# A500_2MB.net
KiCad netlist of a schematic drawn in EAGLE
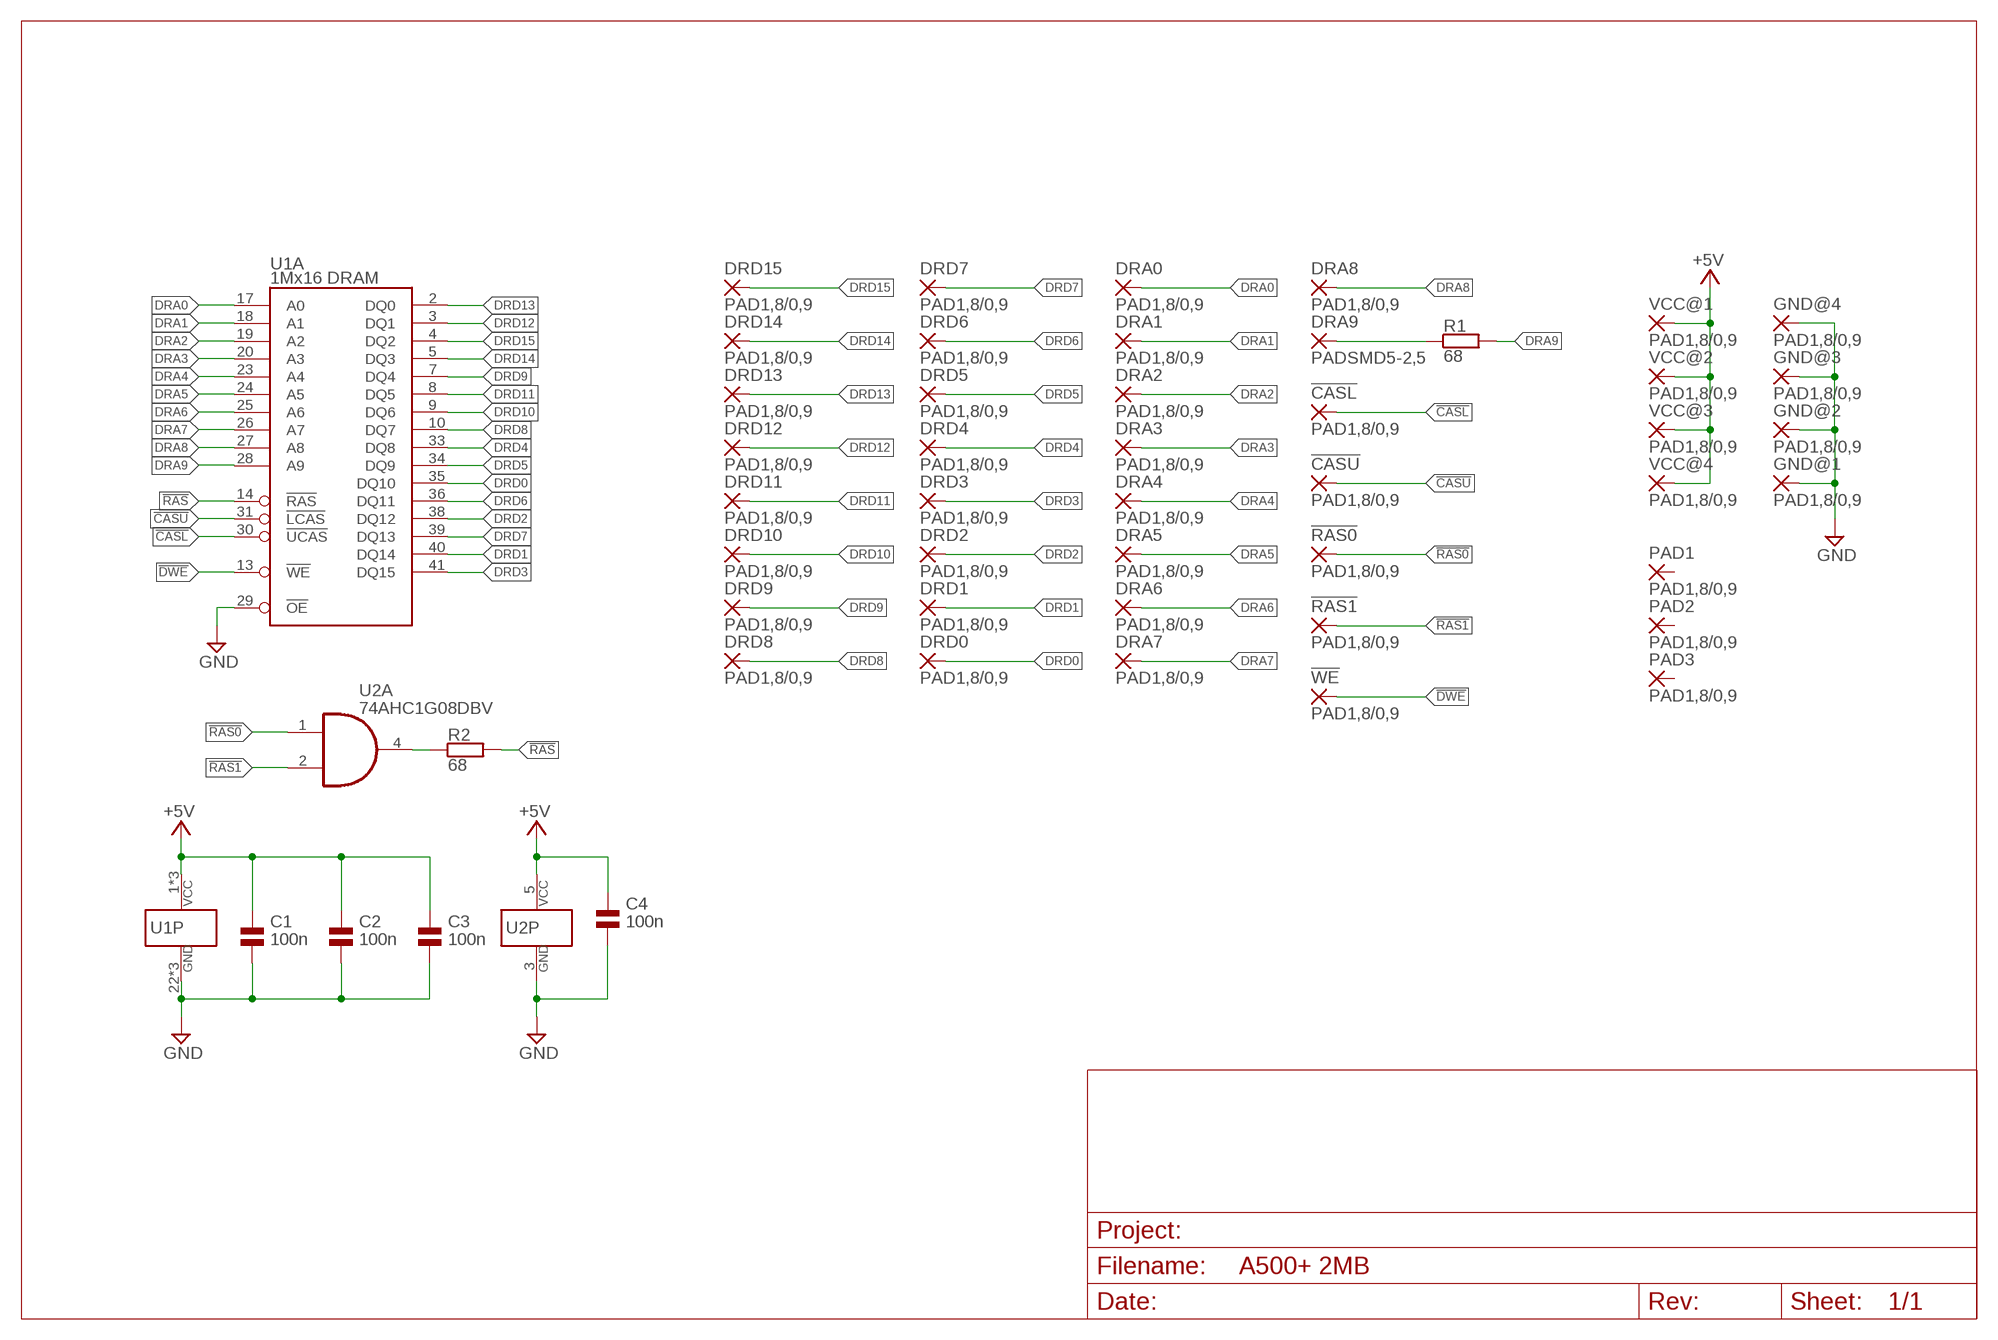
[diagram p0: schematic, sheet 1]

(export (version "E")
  (design (tool "Eeschema 10.0.6"))
  (components
    (comp (ref "!CASL")
      (value "PAD1,8/0,9")
      (footprint "eagle-import:1,8_0,9")
      (libsource (lib "eagle-import") (part "PAD1,8/0,9"))
    )
    (comp (ref "!CASU")
      (value "PAD1,8/0,9")
      (footprint "eagle-import:1,8_0,9")
      (libsource (lib "eagle-import") (part "PAD1,8/0,9"))
    )
    (comp (ref "!RAS0")
      (value "PAD1,8/0,9")
      (footprint "eagle-import:1,8_0,9")
      (libsource (lib "eagle-import") (part "PAD1,8/0,9"))
    )
    (comp (ref "!RAS1")
      (value "PAD1,8/0,9")
      (footprint "eagle-import:1,8_0,9")
      (libsource (lib "eagle-import") (part "PAD1,8/0,9"))
    )
    (comp (ref "!WE")
      (value "PAD1,8/0,9")
      (footprint "eagle-import:1,8_0,9")
      (libsource (lib "eagle-import") (part "PAD1,8/0,9"))
    )
    (comp (ref "C1")
      (value "100n")
      (footprint "eagle-import:0603")
      (libsource (lib "eagle-import") (part "CAP_NPOL0603-"))
    )
    (comp (ref "C2")
      (value "100n")
      (footprint "eagle-import:0603")
      (libsource (lib "eagle-import") (part "CAP_NPOL0603-"))
    )
    (comp (ref "C3")
      (value "100n")
      (footprint "eagle-import:0603")
      (libsource (lib "eagle-import") (part "CAP_NPOL0603-"))
    )
    (comp (ref "C4")
      (value "100n")
      (footprint "eagle-import:0603")
      (libsource (lib "eagle-import") (part "CAP_NPOL0603-"))
    )
    (comp (ref "DRA0")
      (value "PAD1,8/0,9")
      (footprint "eagle-import:1,8_0,9")
      (libsource (lib "eagle-import") (part "PAD1,8/0,9"))
    )
    (comp (ref "DRA1")
      (value "PAD1,8/0,9")
      (footprint "eagle-import:1,8_0,9")
      (libsource (lib "eagle-import") (part "PAD1,8/0,9"))
    )
    (comp (ref "DRA2")
      (value "PAD1,8/0,9")
      (footprint "eagle-import:1,8_0,9")
      (libsource (lib "eagle-import") (part "PAD1,8/0,9"))
    )
    (comp (ref "DRA3")
      (value "PAD1,8/0,9")
      (footprint "eagle-import:1,8_0,9")
      (libsource (lib "eagle-import") (part "PAD1,8/0,9"))
    )
    (comp (ref "DRA4")
      (value "PAD1,8/0,9")
      (footprint "eagle-import:1,8_0,9")
      (libsource (lib "eagle-import") (part "PAD1,8/0,9"))
    )
    (comp (ref "DRA5")
      (value "PAD1,8/0,9")
      (footprint "eagle-import:1,8_0,9")
      (libsource (lib "eagle-import") (part "PAD1,8/0,9"))
    )
    (comp (ref "DRA6")
      (value "PAD1,8/0,9")
      (footprint "eagle-import:1,8_0,9")
      (libsource (lib "eagle-import") (part "PAD1,8/0,9"))
    )
    (comp (ref "DRA7")
      (value "PAD1,8/0,9")
      (footprint "eagle-import:1,8_0,9")
      (libsource (lib "eagle-import") (part "PAD1,8/0,9"))
    )
    (comp (ref "DRA8")
      (value "PAD1,8/0,9")
      (footprint "eagle-import:1,8_0,9")
      (libsource (lib "eagle-import") (part "PAD1,8/0,9"))
    )
    (comp (ref "DRA9")
      (value "PADSMD5-2,5")
      (footprint "eagle-import:5-2,5")
      (libsource (lib "eagle-import") (part "PADSMD5-2,5"))
    )
    (comp (ref "DRD0")
      (value "PAD1,8/0,9")
      (footprint "eagle-import:1,8_0,9")
      (libsource (lib "eagle-import") (part "PAD1,8/0,9"))
    )
    (comp (ref "DRD1")
      (value "PAD1,8/0,9")
      (footprint "eagle-import:1,8_0,9")
      (libsource (lib "eagle-import") (part "PAD1,8/0,9"))
    )
    (comp (ref "DRD2")
      (value "PAD1,8/0,9")
      (footprint "eagle-import:1,8_0,9")
      (libsource (lib "eagle-import") (part "PAD1,8/0,9"))
    )
    (comp (ref "DRD3")
      (value "PAD1,8/0,9")
      (footprint "eagle-import:1,8_0,9")
      (libsource (lib "eagle-import") (part "PAD1,8/0,9"))
    )
    (comp (ref "DRD4")
      (value "PAD1,8/0,9")
      (footprint "eagle-import:1,8_0,9")
      (libsource (lib "eagle-import") (part "PAD1,8/0,9"))
    )
    (comp (ref "DRD5")
      (value "PAD1,8/0,9")
      (footprint "eagle-import:1,8_0,9")
      (libsource (lib "eagle-import") (part "PAD1,8/0,9"))
    )
    (comp (ref "DRD6")
      (value "PAD1,8/0,9")
      (footprint "eagle-import:1,8_0,9")
      (libsource (lib "eagle-import") (part "PAD1,8/0,9"))
    )
    (comp (ref "DRD7")
      (value "PAD1,8/0,9")
      (footprint "eagle-import:1,8_0,9")
      (libsource (lib "eagle-import") (part "PAD1,8/0,9"))
    )
    (comp (ref "DRD8")
      (value "PAD1,8/0,9")
      (footprint "eagle-import:1,8_0,9")
      (libsource (lib "eagle-import") (part "PAD1,8/0,9"))
    )
    (comp (ref "DRD9")
      (value "PAD1,8/0,9")
      (footprint "eagle-import:1,8_0,9")
      (libsource (lib "eagle-import") (part "PAD1,8/0,9"))
    )
    (comp (ref "DRD10")
      (value "PAD1,8/0,9")
      (footprint "eagle-import:1,8_0,9")
      (libsource (lib "eagle-import") (part "PAD1,8/0,9"))
    )
    (comp (ref "DRD11")
      (value "PAD1,8/0,9")
      (footprint "eagle-import:1,8_0,9")
      (libsource (lib "eagle-import") (part "PAD1,8/0,9"))
    )
    (comp (ref "DRD12")
      (value "PAD1,8/0,9")
      (footprint "eagle-import:1,8_0,9")
      (libsource (lib "eagle-import") (part "PAD1,8/0,9"))
    )
    (comp (ref "DRD13")
      (value "PAD1,8/0,9")
      (footprint "eagle-import:1,8_0,9")
      (libsource (lib "eagle-import") (part "PAD1,8/0,9"))
    )
    (comp (ref "DRD14")
      (value "PAD1,8/0,9")
      (footprint "eagle-import:1,8_0,9")
      (libsource (lib "eagle-import") (part "PAD1,8/0,9"))
    )
    (comp (ref "DRD15")
      (value "PAD1,8/0,9")
      (footprint "eagle-import:1,8_0,9")
      (libsource (lib "eagle-import") (part "PAD1,8/0,9"))
    )
    (comp (ref "GND@1")
      (value "PAD1,8/0,9")
      (footprint "eagle-import:1,8_0,9")
      (libsource (lib "eagle-import") (part "PAD1,8/0,9"))
    )
    (comp (ref "GND@2")
      (value "PAD1,8/0,9")
      (footprint "eagle-import:1,8_0,9")
      (libsource (lib "eagle-import") (part "PAD1,8/0,9"))
    )
    (comp (ref "GND@3")
      (value "PAD1,8/0,9")
      (footprint "eagle-import:1,8_0,9")
      (libsource (lib "eagle-import") (part "PAD1,8/0,9"))
    )
    (comp (ref "GND@4")
      (value "PAD1,8/0,9")
      (footprint "eagle-import:1,8_0,9")
      (libsource (lib "eagle-import") (part "PAD1,8/0,9"))
    )
    (comp (ref "PAD1")
      (value "PAD1,8/0,9")
      (footprint "eagle-import:1,8_0,9")
      (libsource (lib "eagle-import") (part "PAD1,8/0,9"))
    )
    (comp (ref "PAD2")
      (value "PAD1,8/0,9")
      (footprint "eagle-import:1,8_0,9")
      (libsource (lib "eagle-import") (part "PAD1,8/0,9"))
    )
    (comp (ref "PAD3")
      (value "PAD1,8/0,9")
      (footprint "eagle-import:1,8_0,9")
      (libsource (lib "eagle-import") (part "PAD1,8/0,9"))
    )
    (comp (ref "R1")
      (value "68")
      (footprint "eagle-import:0603")
      (libsource (lib "eagle-import") (part "RESSMD_0603-"))
    )
    (comp (ref "R2")
      (value "68")
      (footprint "eagle-import:0603")
      (libsource (lib "eagle-import") (part "RESSMD_0603-"))
    )
    (comp (ref "U1")
      (value "1Mx16 DRAM")
      (footprint "eagle-import:SOJ42_4")
      (libsource (lib "eagle-import") (part "DRAM_1MX16SOJ-"))
    )
    (comp (ref "U2")
      (value "74AHC1G08DBV")
      (footprint "eagle-import:SOT23-5")
      (libsource (lib "eagle-import") (part "741G08DBVAHC"))
    )
    (comp (ref "VCC@1")
      (value "PAD1,8/0,9")
      (footprint "eagle-import:1,8_0,9")
      (libsource (lib "eagle-import") (part "PAD1,8/0,9"))
    )
    (comp (ref "VCC@2")
      (value "PAD1,8/0,9")
      (footprint "eagle-import:1,8_0,9")
      (libsource (lib "eagle-import") (part "PAD1,8/0,9"))
    )
    (comp (ref "VCC@3")
      (value "PAD1,8/0,9")
      (footprint "eagle-import:1,8_0,9")
      (libsource (lib "eagle-import") (part "PAD1,8/0,9"))
    )
    (comp (ref "VCC@4")
      (value "PAD1,8/0,9")
      (footprint "eagle-import:1,8_0,9")
      (libsource (lib "eagle-import") (part "PAD1,8/0,9"))
    )
  )
  (nets
    (net (code "1") (name "+5V") (class "Default")
      (node (ref "C1") (pin "1") (pinfunction "1_1") (pintype "passive"))
      (node (ref "C2") (pin "1") (pinfunction "1_1") (pintype "passive"))
      (node (ref "C3") (pin "1") (pinfunction "1_1") (pintype "passive"))
      (node (ref "C4") (pin "1") (pinfunction "1_1") (pintype "passive"))
      (node (ref "U1") (pin "1") (pinfunction "VCC_1") (pintype "power_in"))
      (node (ref "U1") (pin "21") (pinfunction "VCC_21") (pintype "power_in"))
      (node (ref "U1") (pin "6") (pinfunction "VCC_6") (pintype "power_in"))
      (node (ref "U2") (pin "5") (pinfunction "VCC_5") (pintype "power_in"))
      (node (ref "VCC@1") (pin "1") (pinfunction "P_1") (pintype "passive"))
      (node (ref "VCC@2") (pin "1") (pinfunction "P_1") (pintype "passive"))
      (node (ref "VCC@3") (pin "1") (pinfunction "P_1") (pintype "passive"))
      (node (ref "VCC@4") (pin "1") (pinfunction "P_1") (pintype "passive"))
    )
    (net (code "2") (name "/~{CASL}") (class "Default")
      (node (ref "!CASL") (pin "1") (pinfunction "P_1") (pintype "passive"))
      (node (ref "U1") (pin "30") (pinfunction "~{UCAS}_30") (pintype "input"))
    )
    (net (code "3") (name "/~{CASU}") (class "Default")
      (node (ref "!CASU") (pin "1") (pinfunction "P_1") (pintype "passive"))
      (node (ref "U1") (pin "31") (pinfunction "~{LCAS}_31") (pintype "input"))
    )
    (net (code "4") (name "/~{DWE}") (class "Default")
      (node (ref "!WE") (pin "1") (pinfunction "P_1") (pintype "passive"))
      (node (ref "U1") (pin "13") (pinfunction "~{WE}_13") (pintype "input"))
    )
    (net (code "5") (name "/~{RAS0}") (class "Default")
      (node (ref "!RAS0") (pin "1") (pinfunction "P_1") (pintype "passive"))
      (node (ref "U2") (pin "1") (pinfunction "I0_1") (pintype "input"))
    )
    (net (code "6") (name "/~{RAS1}") (class "Default")
      (node (ref "!RAS1") (pin "1") (pinfunction "P_1") (pintype "passive"))
      (node (ref "U2") (pin "2") (pinfunction "I1_2") (pintype "input"))
    )
    (net (code "7") (name "/~{RAS}") (class "Default")
      (node (ref "R2") (pin "2") (pinfunction "2_2") (pintype "passive"))
      (node (ref "U1") (pin "14") (pinfunction "~{RAS}_14") (pintype "input"))
    )
    (net (code "8") (name "DRA0") (class "Default")
      (node (ref "DRA0") (pin "1") (pinfunction "P_1") (pintype "passive"))
      (node (ref "U1") (pin "17") (pinfunction "A0_17") (pintype "input"))
    )
    (net (code "9") (name "DRA1") (class "Default")
      (node (ref "DRA1") (pin "1") (pinfunction "P_1") (pintype "passive"))
      (node (ref "U1") (pin "18") (pinfunction "A1_18") (pintype "input"))
    )
    (net (code "10") (name "DRA2") (class "Default")
      (node (ref "DRA2") (pin "1") (pinfunction "P_1") (pintype "passive"))
      (node (ref "U1") (pin "19") (pinfunction "A2_19") (pintype "input"))
    )
    (net (code "11") (name "DRA3") (class "Default")
      (node (ref "DRA3") (pin "1") (pinfunction "P_1") (pintype "passive"))
      (node (ref "U1") (pin "20") (pinfunction "A3_20") (pintype "input"))
    )
    (net (code "12") (name "DRA4") (class "Default")
      (node (ref "DRA4") (pin "1") (pinfunction "P_1") (pintype "passive"))
      (node (ref "U1") (pin "23") (pinfunction "A4_23") (pintype "input"))
    )
    (net (code "13") (name "DRA5") (class "Default")
      (node (ref "DRA5") (pin "1") (pinfunction "P_1") (pintype "passive"))
      (node (ref "U1") (pin "24") (pinfunction "A5_24") (pintype "input"))
    )
    (net (code "14") (name "DRA6") (class "Default")
      (node (ref "DRA6") (pin "1") (pinfunction "P_1") (pintype "passive"))
      (node (ref "U1") (pin "25") (pinfunction "A6_25") (pintype "input"))
    )
    (net (code "15") (name "DRA7") (class "Default")
      (node (ref "DRA7") (pin "1") (pinfunction "P_1") (pintype "passive"))
      (node (ref "U1") (pin "26") (pinfunction "A7_26") (pintype "input"))
    )
    (net (code "16") (name "DRA8") (class "Default")
      (node (ref "DRA8") (pin "1") (pinfunction "P_1") (pintype "passive"))
      (node (ref "U1") (pin "27") (pinfunction "A8_27") (pintype "input"))
    )
    (net (code "17") (name "DRA9") (class "Default")
      (node (ref "R1") (pin "2") (pinfunction "2_2") (pintype "passive"))
      (node (ref "U1") (pin "28") (pinfunction "A9_28") (pintype "input"))
    )
    (net (code "18") (name "DRD0") (class "Default")
      (node (ref "DRD0") (pin "1") (pinfunction "P_1") (pintype "passive"))
      (node (ref "U1") (pin "35") (pinfunction "DQ10_35") (pintype "bidirectional"))
    )
    (net (code "19") (name "DRD1") (class "Default")
      (node (ref "DRD1") (pin "1") (pinfunction "P_1") (pintype "passive"))
      (node (ref "U1") (pin "40") (pinfunction "DQ14_40") (pintype "bidirectional"))
    )
    (net (code "20") (name "DRD2") (class "Default")
      (node (ref "DRD2") (pin "1") (pinfunction "P_1") (pintype "passive"))
      (node (ref "U1") (pin "38") (pinfunction "DQ12_38") (pintype "bidirectional"))
    )
    (net (code "21") (name "DRD3") (class "Default")
      (node (ref "DRD3") (pin "1") (pinfunction "P_1") (pintype "passive"))
      (node (ref "U1") (pin "41") (pinfunction "DQ15_41") (pintype "bidirectional"))
    )
    (net (code "22") (name "DRD4") (class "Default")
      (node (ref "DRD4") (pin "1") (pinfunction "P_1") (pintype "passive"))
      (node (ref "U1") (pin "33") (pinfunction "DQ8_33") (pintype "bidirectional"))
    )
    (net (code "23") (name "DRD5") (class "Default")
      (node (ref "DRD5") (pin "1") (pinfunction "P_1") (pintype "passive"))
      (node (ref "U1") (pin "34") (pinfunction "DQ9_34") (pintype "bidirectional"))
    )
    (net (code "24") (name "DRD6") (class "Default")
      (node (ref "DRD6") (pin "1") (pinfunction "P_1") (pintype "passive"))
      (node (ref "U1") (pin "36") (pinfunction "DQ11_36") (pintype "bidirectional"))
    )
    (net (code "25") (name "DRD7") (class "Default")
      (node (ref "DRD7") (pin "1") (pinfunction "P_1") (pintype "passive"))
      (node (ref "U1") (pin "39") (pinfunction "DQ13_39") (pintype "bidirectional"))
    )
    (net (code "26") (name "DRD8") (class "Default")
      (node (ref "DRD8") (pin "1") (pinfunction "P_1") (pintype "passive"))
      (node (ref "U1") (pin "10") (pinfunction "DQ7_10") (pintype "bidirectional"))
    )
    (net (code "27") (name "DRD9") (class "Default")
      (node (ref "DRD9") (pin "1") (pinfunction "P_1") (pintype "passive"))
      (node (ref "U1") (pin "7") (pinfunction "DQ4_7") (pintype "bidirectional"))
    )
    (net (code "28") (name "DRD10") (class "Default")
      (node (ref "DRD10") (pin "1") (pinfunction "P_1") (pintype "passive"))
      (node (ref "U1") (pin "9") (pinfunction "DQ6_9") (pintype "bidirectional"))
    )
    (net (code "29") (name "DRD11") (class "Default")
      (node (ref "DRD11") (pin "1") (pinfunction "P_1") (pintype "passive"))
      (node (ref "U1") (pin "8") (pinfunction "DQ5_8") (pintype "bidirectional"))
    )
    (net (code "30") (name "DRD12") (class "Default")
      (node (ref "DRD12") (pin "1") (pinfunction "P_1") (pintype "passive"))
      (node (ref "U1") (pin "3") (pinfunction "DQ1_3") (pintype "bidirectional"))
    )
    (net (code "31") (name "DRD13") (class "Default")
      (node (ref "DRD13") (pin "1") (pinfunction "P_1") (pintype "passive"))
      (node (ref "U1") (pin "2") (pinfunction "DQ0_2") (pintype "bidirectional"))
    )
    (net (code "32") (name "DRD14") (class "Default")
      (node (ref "DRD14") (pin "1") (pinfunction "P_1") (pintype "passive"))
      (node (ref "U1") (pin "5") (pinfunction "DQ3_5") (pintype "bidirectional"))
    )
    (net (code "33") (name "DRD15") (class "Default")
      (node (ref "DRD15") (pin "1") (pinfunction "P_1") (pintype "passive"))
      (node (ref "U1") (pin "4") (pinfunction "DQ2_4") (pintype "bidirectional"))
    )
    (net (code "34") (name "GND") (class "Default")
      (node (ref "C1") (pin "2") (pinfunction "2_2") (pintype "passive"))
      (node (ref "C2") (pin "2") (pinfunction "2_2") (pintype "passive"))
      (node (ref "C3") (pin "2") (pinfunction "2_2") (pintype "passive"))
      (node (ref "C4") (pin "2") (pinfunction "2_2") (pintype "passive"))
      (node (ref "GND@1") (pin "1") (pinfunction "P_1") (pintype "passive"))
      (node (ref "GND@2") (pin "1") (pinfunction "P_1") (pintype "passive"))
      (node (ref "GND@3") (pin "1") (pinfunction "P_1") (pintype "passive"))
      (node (ref "GND@4") (pin "1") (pinfunction "P_1") (pintype "passive"))
      (node (ref "U1") (pin "22") (pinfunction "GND_22") (pintype "power_in"))
      (node (ref "U1") (pin "29") (pinfunction "~{OE}_29") (pintype "input"))
      (node (ref "U1") (pin "37") (pinfunction "GND_37") (pintype "power_in"))
      (node (ref "U1") (pin "42") (pinfunction "GND_42") (pintype "power_in"))
      (node (ref "U2") (pin "3") (pinfunction "GND_3") (pintype "power_in"))
    )
    (net (code "35") (name "Net-(DRA9-P)") (class "Default")
      (node (ref "DRA9") (pin "1") (pinfunction "P_1") (pintype "passive"))
      (node (ref "R1") (pin "1") (pinfunction "1_1") (pintype "passive"))
    )
    (net (code "36") (name "Net-(U2A-O)") (class "Default")
      (node (ref "R2") (pin "1") (pinfunction "1_1") (pintype "passive"))
      (node (ref "U2") (pin "4") (pinfunction "O_4") (pintype "output"))
    )
    (net (code "37") (name "unconnected-(PAD1-P-Pad1)") (class "Default")
      (node (ref "PAD1") (pin "1") (pinfunction "P_1") (pintype "passive"))
    )
    (net (code "38") (name "unconnected-(PAD2-P-Pad1)") (class "Default")
      (node (ref "PAD2") (pin "1") (pinfunction "P_1") (pintype "passive"))
    )
    (net (code "39") (name "unconnected-(PAD3-P-Pad1)") (class "Default")
      (node (ref "PAD3") (pin "1") (pinfunction "P_1") (pintype "passive"))
    )
  )
)
